# Core.net
KiCad netlist of a schematic drawn in Altium Designer
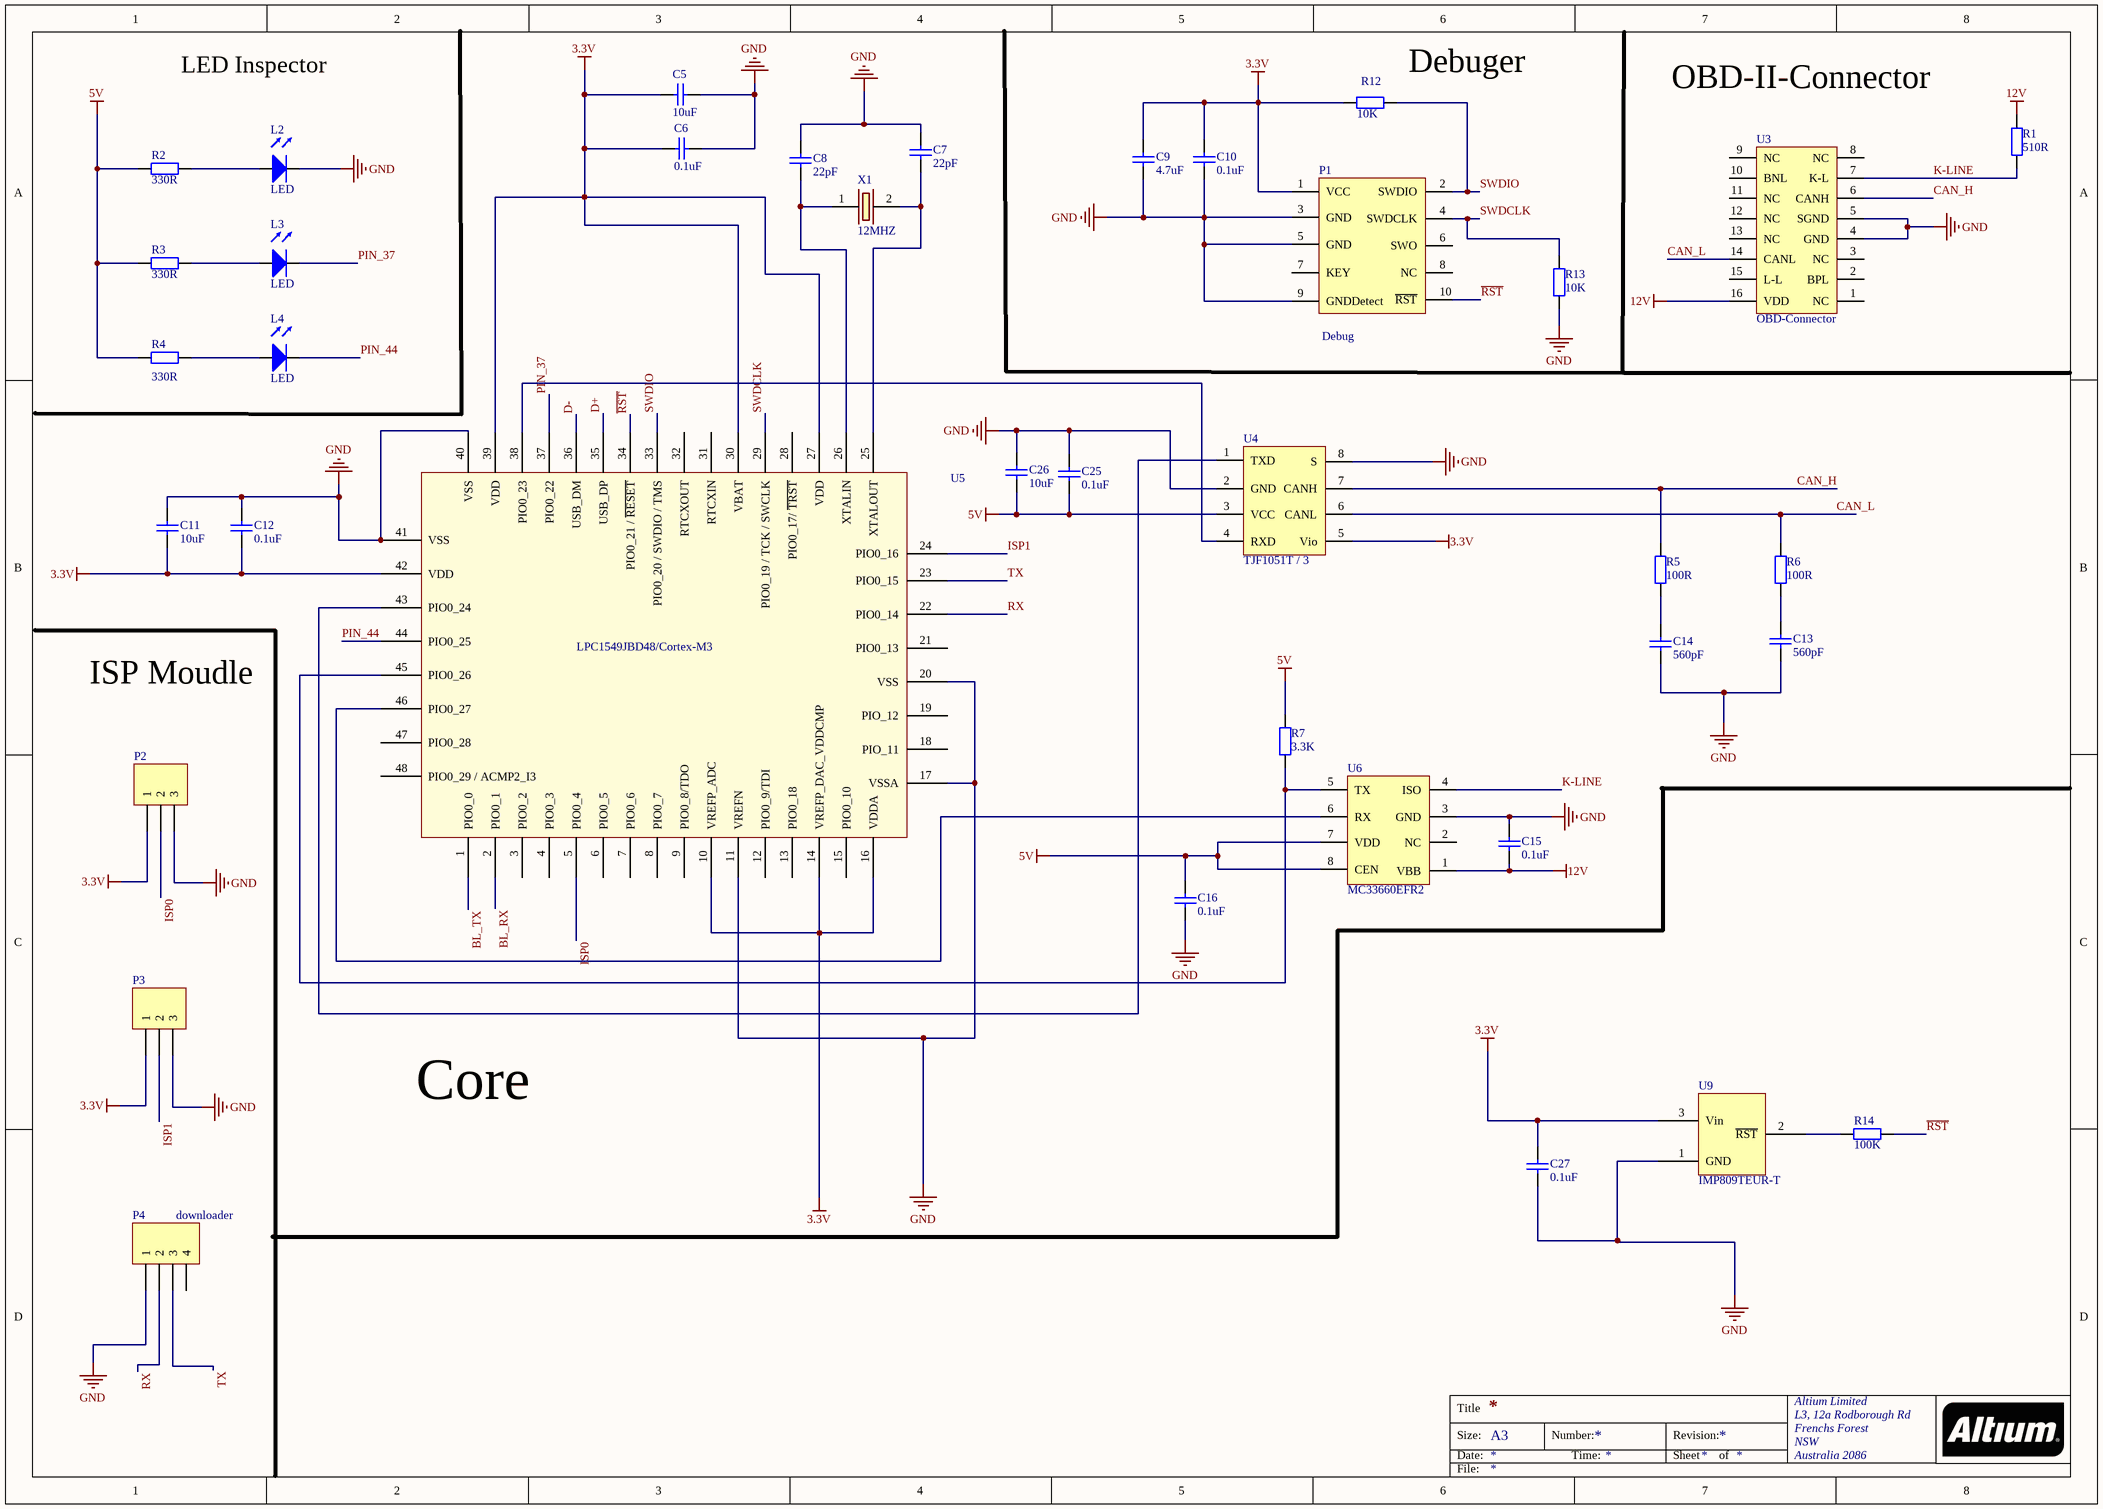
[diagram p0: Core.SchDoc]

(export (version "E")
  (design (tool "Eeschema 10.0.6"))
  (components
    (comp (ref "C5")
      (value "10uF")
      (footprint "0603")
      (description "ceramic")
      (libsource (lib "ToponLib") (part "Cap1"))
    )
    (comp (ref "C6")
      (value "0.1uF")
      (footprint "0603")
      (description "ceramic")
      (libsource (lib "ToponLib") (part "Cap1"))
    )
    (comp (ref "C7")
      (value "22pF")
      (footprint "0603")
      (description "ceramic")
      (libsource (lib "ToponLib") (part "Cap1"))
    )
    (comp (ref "C8")
      (value "22pF")
      (footprint "0603")
      (description "ceramic")
      (libsource (lib "ToponLib") (part "Cap1"))
    )
    (comp (ref "C9")
      (value "4.7uF")
      (footprint "0603")
      (description "ceramic")
      (libsource (lib "ToponLib") (part "Cap1"))
    )
    (comp (ref "C10")
      (value "0.1uF")
      (footprint "0603")
      (description "ceramic")
      (libsource (lib "ToponLib") (part "Cap1"))
    )
    (comp (ref "C11")
      (value "10uF")
      (footprint "0603")
      (description "ceramic")
      (libsource (lib "ToponLib") (part "Cap1"))
    )
    (comp (ref "C12")
      (value "0.1uF")
      (footprint "0603")
      (description "ceramic")
      (libsource (lib "ToponLib") (part "Cap1"))
    )
    (comp (ref "C13")
      (value "560pF")
      (footprint "0603")
      (description "ceramic")
      (libsource (lib "ToponLib") (part "Cap1"))
    )
    (comp (ref "C14")
      (value "560pF")
      (footprint "0603")
      (description "ceramic")
      (libsource (lib "ToponLib") (part "Cap1"))
    )
    (comp (ref "C15")
      (value "0.1uF")
      (footprint "0603")
      (description "ceramic")
      (libsource (lib "ToponLib") (part "Cap1"))
    )
    (comp (ref "C16")
      (value "0.1uF")
      (footprint "0603")
      (description "ceramic")
      (libsource (lib "ToponLib") (part "Cap1"))
    )
    (comp (ref "C25")
      (value "0.1uF")
      (footprint "0603")
      (description "ceramic")
      (libsource (lib "ToponLib") (part "Cap1"))
    )
    (comp (ref "C26")
      (value "10uF")
      (footprint "0603")
      (description "ceramic")
      (libsource (lib "ToponLib") (part "Cap1"))
    )
    (comp (ref "C27")
      (value "0.1uF")
      (footprint "0603")
      (description "ceramic")
      (libsource (lib "ToponLib") (part "Cap1"))
    )
    (comp (ref "L2") (value "LED") (footprint "0805") (libsource (lib "ToponLib") (part "LED")))
    (comp (ref "L3") (value "LED") (footprint "0805") (libsource (lib "ToponLib") (part "LED")))
    (comp (ref "L4") (value "LED") (footprint "0805") (libsource (lib "ToponLib") (part "LED")))
    (comp (ref "P1")
      (value "Debug")
      (footprint "JATG_10pin")
      (libsource (lib "ToponLib") (part "JTAG_10Pin"))
    )
    (comp (ref "P2")
      (value "~")
      (footprint "HDR1X3")
      (description "Header, 3-Pin")
      (fields (field (name "PUBLISHER") "Altium Limited"))
      (libsource (lib "Miscellaneous Connectors") (part "Header 3"))
    )
    (comp (ref "P3")
      (value "~")
      (footprint "HDR1X3")
      (description "Header, 3-Pin")
      (fields (field (name "PUBLISHER") "Altium Limited"))
      (libsource (lib "Miscellaneous Connectors") (part "Header 3"))
    )
    (comp (ref "P4")
      (value "downloader")
      (footprint "HDR1X4")
      (description "Header, 4-Pin")
      (fields (field (name "PUBLISHER") "Altium Limited"))
      (libsource (lib "Miscellaneous Connectors") (part "Header 4"))
    )
    (comp (ref "R1") (value "510R") (footprint "0603") (libsource (lib "ToponLib") (part "Res")))
    (comp (ref "R2") (value "330R") (footprint "0603") (libsource (lib "") (part "Res_1")))
    (comp (ref "R3") (value "330R") (footprint "0603") (libsource (lib "") (part "Res_1")))
    (comp (ref "R4") (value "330R") (footprint "0603") (libsource (lib "") (part "Res_1")))
    (comp (ref "R5") (value "100R") (footprint "0603") (libsource (lib "ToponLib") (part "Res")))
    (comp (ref "R6") (value "100R") (footprint "0603") (libsource (lib "ToponLib") (part "Res")))
    (comp (ref "R7") (value "3.3K") (footprint "0603") (libsource (lib "ToponLib") (part "Res")))
    (comp (ref "R12") (value "10K") (footprint "0603") (libsource (lib "") (part "Res_1")))
    (comp (ref "R13") (value "10K") (footprint "0603") (libsource (lib "ToponLib") (part "Res")))
    (comp (ref "R14") (value "100K") (footprint "0603") (libsource (lib "") (part "Res_2")))
    (comp (ref "U3")
      (value "OBD-Connector")
      (footprint "OBD-MaleConnector")
      (libsource (lib "ToponLib") (part "OBD-MaleHead"))
    )
    (comp (ref "U4")
      (value "TJF1051T / 3")
      (footprint "TJF1051")
      (libsource (lib "ToponLib") (part "TJF1051T / 3"))
    )
    (comp (ref "U5")
      (value "LPC1549")
      (footprint "LPC1549JBD48")
      (libsource (lib "ToponLib") (part "LPC1549JBD48"))
    )
    (comp (ref "U6")
      (value "MC33660EFR2")
      (footprint "SOP-8")
      (libsource (lib "ToponLib") (part "MC33660EFR2"))
    )
    (comp (ref "U9")
      (value "IMP809TEUR-T")
      (footprint "SOT23-3")
      (libsource (lib "ToponLib") (part "IMP809TEUR-T"))
    )
    (comp (ref "X1") (value "12MHZ") (footprint "12Mhz-DFN") (libsource (lib "ToponLib") (part "OSC")))
  )
  (nets
    (net (code "1") (name "/BL_RX") (class "Default")
      (node (ref "U5") (pin "2") (pinfunction "PIO0_1_2") (pintype "passive"))
    )
    (net (code "2") (name "/BL_TX") (class "Default")
      (node (ref "U5") (pin "1") (pinfunction "PIO0_0_1") (pintype "passive"))
    )
    (net (code "3") (name "/CAN_H") (class "Default")
      (node (ref "R5") (pin "2") (pinfunction "2_2") (pintype "passive"))
      (node (ref "U3") (pin "6") (pinfunction "CANH_6") (pintype "passive"))
      (node (ref "U4") (pin "7") (pinfunction "CANH_7") (pintype "passive"))
    )
    (net (code "4") (name "/CAN_L") (class "Default")
      (node (ref "R6") (pin "2") (pinfunction "2_2") (pintype "passive"))
      (node (ref "U3") (pin "14") (pinfunction "CANL_14") (pintype "passive"))
      (node (ref "U4") (pin "6") (pinfunction "CANL_6") (pintype "passive"))
    )
    (net (code "5") (name "/D+") (class "Default")
      (node (ref "U5") (pin "35") (pinfunction "USB_DP_35") (pintype "passive"))
    )
    (net (code "6") (name "/D-") (class "Default")
      (node (ref "U5") (pin "36") (pinfunction "USB_DM_36") (pintype "passive"))
    )
    (net (code "7") (name "/ISP0") (class "Default")
      (node (ref "P2") (pin "2") (pinfunction "2_2") (pintype "passive"))
      (node (ref "U5") (pin "5") (pinfunction "PIO0_4_5") (pintype "passive"))
    )
    (net (code "8") (name "/ISP1") (class "Default")
      (node (ref "P3") (pin "2") (pinfunction "2_2") (pintype "passive"))
      (node (ref "U5") (pin "24") (pinfunction "PIO0_16_24") (pintype "passive"))
    )
    (net (code "9") (name "/K-LINE") (class "Default")
      (node (ref "R1") (pin "1") (pinfunction "1_1") (pintype "passive"))
      (node (ref "U3") (pin "7") (pinfunction "K-L_7") (pintype "passive"))
      (node (ref "U6") (pin "4") (pinfunction "ISO_4") (pintype "passive"))
    )
    (net (code "10") (name "/PIN_37") (class "Default")
      (node (ref "L3") (pin "2") (pinfunction "K_2") (pintype "passive"))
      (node (ref "U5") (pin "37") (pinfunction "PIO0_22_37") (pintype "passive"))
    )
    (net (code "11") (name "/PIN_44") (class "Default")
      (node (ref "L4") (pin "2") (pinfunction "K_2") (pintype "passive"))
      (node (ref "U5") (pin "44") (pinfunction "PIO0_25_44") (pintype "passive"))
    )
    (net (code "12") (name "/RX") (class "Default")
      (node (ref "P4") (pin "2") (pinfunction "2_2") (pintype "passive"))
      (node (ref "U5") (pin "22") (pinfunction "PIO0_14_22") (pintype "passive"))
    )
    (net (code "13") (name "/SWDCLK") (class "Default")
      (node (ref "P1") (pin "4") (pinfunction "SWDCLK_4") (pintype "passive"))
      (node (ref "R13") (pin "2") (pinfunction "2_2") (pintype "passive"))
      (node (ref "U5") (pin "29") (pinfunction "PIO0_19_/_TCK_/_SWCLK_29") (pintype "passive"))
    )
    (net (code "14") (name "/SWDIO") (class "Default")
      (node (ref "P1") (pin "2") (pinfunction "SWDIO_2") (pintype "passive"))
      (node (ref "R12") (pin "2") (pinfunction "2_2") (pintype "passive"))
      (node (ref "U5") (pin "33") (pinfunction "PIO0_20_/_SWDIO_/_TMS_33") (pintype "passive"))
    )
    (net (code "15") (name "/TX") (class "Default")
      (node (ref "P4") (pin "3") (pinfunction "3_3") (pintype "passive"))
      (node (ref "U5") (pin "23") (pinfunction "PIO0_15_23") (pintype "passive"))
    )
    (net (code "16") (name "/~{RST}") (class "Default")
      (node (ref "P1") (pin "10") (pinfunction "~{RST}_10") (pintype "passive"))
      (node (ref "R14") (pin "1") (pinfunction "1_1") (pintype "passive"))
      (node (ref "U5") (pin "34") (pinfunction "PIO0_21_/_~{RESET}_34") (pintype "passive"))
    )
    (net (code "17") (name "3.3V") (class "Default")
      (node (ref "C10") (pin "2") (pinfunction "2_2") (pintype "passive"))
      (node (ref "C11") (pin "1") (pinfunction "1_1") (pintype "passive"))
      (node (ref "C12") (pin "1") (pinfunction "1_1") (pintype "passive"))
      (node (ref "C27") (pin "2") (pinfunction "2_2") (pintype "passive"))
      (node (ref "C5") (pin "2") (pinfunction "2_2") (pintype "passive"))
      (node (ref "C6") (pin "2") (pinfunction "2_2") (pintype "passive"))
      (node (ref "C9") (pin "2") (pinfunction "2_2") (pintype "passive"))
      (node (ref "P1") (pin "1") (pinfunction "VCC_1") (pintype "passive"))
      (node (ref "P2") (pin "1") (pinfunction "1_1") (pintype "passive"))
      (node (ref "P3") (pin "1") (pinfunction "1_1") (pintype "passive"))
      (node (ref "R12") (pin "1") (pinfunction "1_1") (pintype "passive"))
      (node (ref "U4") (pin "5") (pinfunction "Vio_5") (pintype "passive"))
      (node (ref "U5") (pin "10") (pinfunction "VREFP_ADC_10") (pintype "passive"))
      (node (ref "U5") (pin "14") (pinfunction "VREFP_DAC_VDDCMP_14") (pintype "passive"))
      (node (ref "U5") (pin "16") (pinfunction "VDDA_16") (pintype "passive"))
      (node (ref "U5") (pin "27") (pinfunction "VDD_27") (pintype "passive"))
      (node (ref "U5") (pin "30") (pinfunction "VBAT_30") (pintype "passive"))
      (node (ref "U5") (pin "39") (pinfunction "VDD_39") (pintype "passive"))
      (node (ref "U5") (pin "42") (pinfunction "VDD_42") (pintype "passive"))
      (node (ref "U9") (pin "3") (pinfunction "Vin_3") (pintype "passive"))
    )
    (net (code "18") (name "5V") (class "Default")
      (node (ref "C16") (pin "2") (pinfunction "2_2") (pintype "passive"))
      (node (ref "C25") (pin "1") (pinfunction "1_1") (pintype "passive"))
      (node (ref "C26") (pin "1") (pinfunction "1_1") (pintype "passive"))
      (node (ref "R2") (pin "1") (pinfunction "1_1") (pintype "passive"))
      (node (ref "R3") (pin "1") (pinfunction "1_1") (pintype "passive"))
      (node (ref "R4") (pin "1") (pinfunction "1_1") (pintype "passive"))
      (node (ref "R7") (pin "2") (pinfunction "2_2") (pintype "passive"))
      (node (ref "U4") (pin "3") (pinfunction "VCC_3") (pintype "passive"))
      (node (ref "U6") (pin "7") (pinfunction "VDD_7") (pintype "passive"))
      (node (ref "U6") (pin "8") (pinfunction "CEN_8") (pintype "passive"))
    )
    (net (code "19") (name "12V") (class "Default")
      (node (ref "C15") (pin "1") (pinfunction "1_1") (pintype "passive"))
      (node (ref "R1") (pin "2") (pinfunction "2_2") (pintype "passive"))
      (node (ref "U3") (pin "16") (pinfunction "VDD_16") (pintype "passive"))
      (node (ref "U6") (pin "1") (pinfunction "VBB_1") (pintype "passive"))
    )
    (net (code "20") (name "GND") (class "Default")
      (node (ref "C10") (pin "1") (pinfunction "1_1") (pintype "passive"))
      (node (ref "C11") (pin "2") (pinfunction "2_2") (pintype "passive"))
      (node (ref "C12") (pin "2") (pinfunction "2_2") (pintype "passive"))
      (node (ref "C13") (pin "1") (pinfunction "1_1") (pintype "passive"))
      (node (ref "C14") (pin "1") (pinfunction "1_1") (pintype "passive"))
      (node (ref "C15") (pin "2") (pinfunction "2_2") (pintype "passive"))
      (node (ref "C16") (pin "1") (pinfunction "1_1") (pintype "passive"))
      (node (ref "C25") (pin "2") (pinfunction "2_2") (pintype "passive"))
      (node (ref "C26") (pin "2") (pinfunction "2_2") (pintype "passive"))
      (node (ref "C27") (pin "1") (pinfunction "1_1") (pintype "passive"))
      (node (ref "C5") (pin "1") (pinfunction "1_1") (pintype "passive"))
      (node (ref "C6") (pin "1") (pinfunction "1_1") (pintype "passive"))
      (node (ref "C7") (pin "2") (pinfunction "2_2") (pintype "passive"))
      (node (ref "C8") (pin "2") (pinfunction "2_2") (pintype "passive"))
      (node (ref "C9") (pin "1") (pinfunction "1_1") (pintype "passive"))
      (node (ref "L2") (pin "2") (pinfunction "K_2") (pintype "passive"))
      (node (ref "P1") (pin "3") (pinfunction "GND_3") (pintype "passive"))
      (node (ref "P1") (pin "5") (pinfunction "GND_5") (pintype "passive"))
      (node (ref "P1") (pin "9") (pinfunction "GNDDetect_9") (pintype "passive"))
      (node (ref "P2") (pin "3") (pinfunction "3_3") (pintype "passive"))
      (node (ref "P3") (pin "3") (pinfunction "3_3") (pintype "passive"))
      (node (ref "P4") (pin "1") (pinfunction "1_1") (pintype "passive"))
      (node (ref "R13") (pin "1") (pinfunction "1_1") (pintype "passive"))
      (node (ref "U3") (pin "4") (pinfunction "GND_4") (pintype "passive"))
      (node (ref "U3") (pin "5") (pinfunction "SGND_5") (pintype "passive"))
      (node (ref "U4") (pin "2") (pinfunction "GND_2") (pintype "passive"))
      (node (ref "U4") (pin "8") (pinfunction "S_8") (pintype "passive"))
      (node (ref "U5") (pin "11") (pinfunction "VREFN_11") (pintype "passive"))
      (node (ref "U5") (pin "17") (pinfunction "VSSA_17") (pintype "passive"))
      (node (ref "U5") (pin "20") (pinfunction "VSS_20") (pintype "passive"))
      (node (ref "U5") (pin "40") (pinfunction "VSS_40") (pintype "passive"))
      (node (ref "U5") (pin "41") (pinfunction "VSS_41") (pintype "passive"))
      (node (ref "U6") (pin "3") (pinfunction "GND_3") (pintype "passive"))
      (node (ref "U9") (pin "1") (pinfunction "GND_1") (pintype "passive"))
    )
    (net (code "21") (name "Net-(C13-Pad2)") (class "Default")
      (node (ref "C13") (pin "2") (pinfunction "2_2") (pintype "passive"))
      (node (ref "R6") (pin "1") (pinfunction "1_1") (pintype "passive"))
    )
    (net (code "22") (name "Net-(C14-Pad2)") (class "Default")
      (node (ref "C14") (pin "2") (pinfunction "2_2") (pintype "passive"))
      (node (ref "R5") (pin "1") (pinfunction "1_1") (pintype "passive"))
    )
    (net (code "23") (name "Net-(L2-A)") (class "Default")
      (node (ref "L2") (pin "1") (pinfunction "A_1") (pintype "passive"))
      (node (ref "R2") (pin "2") (pinfunction "2_2") (pintype "passive"))
    )
    (net (code "24") (name "Net-(L3-A)") (class "Default")
      (node (ref "L3") (pin "1") (pinfunction "A_1") (pintype "passive"))
      (node (ref "R3") (pin "2") (pinfunction "2_2") (pintype "passive"))
    )
    (net (code "25") (name "Net-(L4-A)") (class "Default")
      (node (ref "L4") (pin "1") (pinfunction "A_1") (pintype "passive"))
      (node (ref "R4") (pin "2") (pinfunction "2_2") (pintype "passive"))
    )
    (net (code "26") (name "Net-(U4-RXD)") (class "Default")
      (node (ref "U4") (pin "4") (pinfunction "RXD_4") (pintype "passive"))
      (node (ref "U5") (pin "38") (pinfunction "PIO0_23_38") (pintype "passive"))
    )
    (net (code "27") (name "Net-(U4-TXD)") (class "Default")
      (node (ref "U4") (pin "1") (pinfunction "TXD_1") (pintype "passive"))
      (node (ref "U5") (pin "43") (pinfunction "PIO0_24_43") (pintype "passive"))
    )
    (net (code "28") (name "Net-(U5-PIO0_26)") (class "Default")
      (node (ref "R7") (pin "1") (pinfunction "1_1") (pintype "passive"))
      (node (ref "U5") (pin "45") (pinfunction "PIO0_26_45") (pintype "passive"))
      (node (ref "U6") (pin "5") (pinfunction "TX_5") (pintype "passive"))
    )
    (net (code "29") (name "Net-(U5-PIO0_27)") (class "Default")
      (node (ref "U5") (pin "46") (pinfunction "PIO0_27_46") (pintype "passive"))
      (node (ref "U6") (pin "6") (pinfunction "RX_6") (pintype "passive"))
    )
    (net (code "30") (name "Net-(U5-XTALIN)") (class "Default")
      (node (ref "C8") (pin "1") (pinfunction "1_1") (pintype "passive"))
      (node (ref "U5") (pin "26") (pinfunction "XTALIN_26") (pintype "passive"))
      (node (ref "X1") (pin "1") (pinfunction "1_1") (pintype "passive"))
    )
    (net (code "31") (name "Net-(U5-XTALOUT)") (class "Default")
      (node (ref "C7") (pin "1") (pinfunction "1_1") (pintype "passive"))
      (node (ref "U5") (pin "25") (pinfunction "XTALOUT_25") (pintype "passive"))
      (node (ref "X1") (pin "2") (pinfunction "2_2") (pintype "passive"))
    )
    (net (code "32") (name "Net-(U9-~{RST})") (class "Default")
      (node (ref "R14") (pin "2") (pinfunction "2_2") (pintype "passive"))
      (node (ref "U9") (pin "2") (pinfunction "~{RST}_2") (pintype "passive"))
    )
    (net (code "33") (name "unconnected-(P1-KEY-Pad7)") (class "Default")
      (node (ref "P1") (pin "7") (pinfunction "KEY_7") (pintype "passive"))
    )
    (net (code "34") (name "unconnected-(P1-NC-Pad8)") (class "Default")
      (node (ref "P1") (pin "8") (pinfunction "NC_8") (pintype "passive"))
    )
    (net (code "35") (name "unconnected-(P1-SWO-Pad6)") (class "Default")
      (node (ref "P1") (pin "6") (pinfunction "SWO_6") (pintype "passive"))
    )
    (net (code "36") (name "unconnected-(P4-Pad4)") (class "Default")
      (node (ref "P4") (pin "4") (pinfunction "4_4") (pintype "passive"))
    )
    (net (code "37") (name "unconnected-(U3-BNL-Pad10)") (class "Default")
      (node (ref "U3") (pin "10") (pinfunction "BNL_10") (pintype "passive"))
    )
    (net (code "38") (name "unconnected-(U3-BPL-Pad2)") (class "Default")
      (node (ref "U3") (pin "2") (pinfunction "BPL_2") (pintype "passive"))
    )
    (net (code "39") (name "unconnected-(U3-L-L-Pad15)") (class "Default")
      (node (ref "U3") (pin "15") (pinfunction "L-L_15") (pintype "passive"))
    )
    (net (code "40") (name "unconnected-(U3-NC-Pad1)") (class "Default")
      (node (ref "U3") (pin "1") (pinfunction "NC_1") (pintype "passive"))
    )
    (net (code "41") (name "unconnected-(U3-NC-Pad3)") (class "Default")
      (node (ref "U3") (pin "3") (pinfunction "NC_3") (pintype "passive"))
    )
    (net (code "42") (name "unconnected-(U3-NC-Pad8)") (class "Default")
      (node (ref "U3") (pin "8") (pinfunction "NC_8") (pintype "passive"))
    )
    (net (code "43") (name "unconnected-(U3-NC-Pad9)") (class "Default")
      (node (ref "U3") (pin "9") (pinfunction "NC_9") (pintype "passive"))
    )
    (net (code "44") (name "unconnected-(U3-NC-Pad11)") (class "Default")
      (node (ref "U3") (pin "11") (pinfunction "NC_11") (pintype "passive"))
    )
    (net (code "45") (name "unconnected-(U3-NC-Pad12)") (class "Default")
      (node (ref "U3") (pin "12") (pinfunction "NC_12") (pintype "passive"))
    )
    (net (code "46") (name "unconnected-(U3-NC-Pad13)") (class "Default")
      (node (ref "U3") (pin "13") (pinfunction "NC_13") (pintype "passive"))
    )
    (net (code "47") (name "unconnected-(U5-PIO0_2-Pad3)") (class "Default")
      (node (ref "U5") (pin "3") (pinfunction "PIO0_2_3") (pintype "passive"))
    )
    (net (code "48") (name "unconnected-(U5-PIO0_3-Pad4)") (class "Default")
      (node (ref "U5") (pin "4") (pinfunction "PIO0_3_4") (pintype "passive"))
    )
    (net (code "49") (name "unconnected-(U5-PIO0_5-Pad6)") (class "Default")
      (node (ref "U5") (pin "6") (pinfunction "PIO0_5_6") (pintype "passive"))
    )
    (net (code "50") (name "unconnected-(U5-PIO0_6-Pad7)") (class "Default")
      (node (ref "U5") (pin "7") (pinfunction "PIO0_6_7") (pintype "passive"))
    )
    (net (code "51") (name "unconnected-(U5-PIO0_7-Pad8)") (class "Default")
      (node (ref "U5") (pin "8") (pinfunction "PIO0_7_8") (pintype "passive"))
    )
    (net (code "52") (name "unconnected-(U5-PIO0_8{slash}TDO-Pad9)") (class "Default")
      (node (ref "U5") (pin "9") (pinfunction "PIO0_8/TDO_9") (pintype "passive"))
    )
    (net (code "53") (name "unconnected-(U5-PIO0_9{slash}TDI-Pad12)") (class "Default")
      (node (ref "U5") (pin "12") (pinfunction "PIO0_9/TDI_12") (pintype "passive"))
    )
    (net (code "54") (name "unconnected-(U5-PIO0_10-Pad15)") (class "Default")
      (node (ref "U5") (pin "15") (pinfunction "PIO0_10_15") (pintype "passive"))
    )
    (net (code "55") (name "unconnected-(U5-PIO0_13-Pad21)") (class "Default")
      (node (ref "U5") (pin "21") (pinfunction "PIO0_13_21") (pintype "passive"))
    )
    (net (code "56") (name "unconnected-(U5-PIO0_17{slash}_~{TRST}-Pad28)") (class "Default")
      (node (ref "U5") (pin "28") (pinfunction "PIO0_17/_~{TRST}_28") (pintype "passive"))
    )
    (net (code "57") (name "unconnected-(U5-PIO0_18-Pad13)") (class "Default")
      (node (ref "U5") (pin "13") (pinfunction "PIO0_18_13") (pintype "passive"))
    )
    (net (code "58") (name "unconnected-(U5-PIO0_28-Pad47)") (class "Default")
      (node (ref "U5") (pin "47") (pinfunction "PIO0_28_47") (pintype "passive"))
    )
    (net (code "59") (name "unconnected-(U5-PIO0_29_{slash}_ACMP2_I3-Pad48)") (class "Default")
      (node (ref "U5") (pin "48") (pinfunction "PIO0_29_/_ACMP2_I3_48") (pintype "passive"))
    )
    (net (code "60") (name "unconnected-(U5-PIO_11-Pad18)") (class "Default")
      (node (ref "U5") (pin "18") (pinfunction "PIO_11_18") (pintype "passive"))
    )
    (net (code "61") (name "unconnected-(U5-PIO_12-Pad19)") (class "Default")
      (node (ref "U5") (pin "19") (pinfunction "PIO_12_19") (pintype "passive"))
    )
    (net (code "62") (name "unconnected-(U5-RTCXIN-Pad31)") (class "Default")
      (node (ref "U5") (pin "31") (pinfunction "RTCXIN_31") (pintype "passive"))
    )
    (net (code "63") (name "unconnected-(U5-RTCXOUT-Pad32)") (class "Default")
      (node (ref "U5") (pin "32") (pinfunction "RTCXOUT_32") (pintype "passive"))
    )
    (net (code "64") (name "unconnected-(U6-NC-Pad2)") (class "Default")
      (node (ref "U6") (pin "2") (pinfunction "NC_2") (pintype "passive"))
    )
  )
)
